# L002_-_Square_-_Schematic.net
KiCad netlist of a schematic drawn in EAGLE
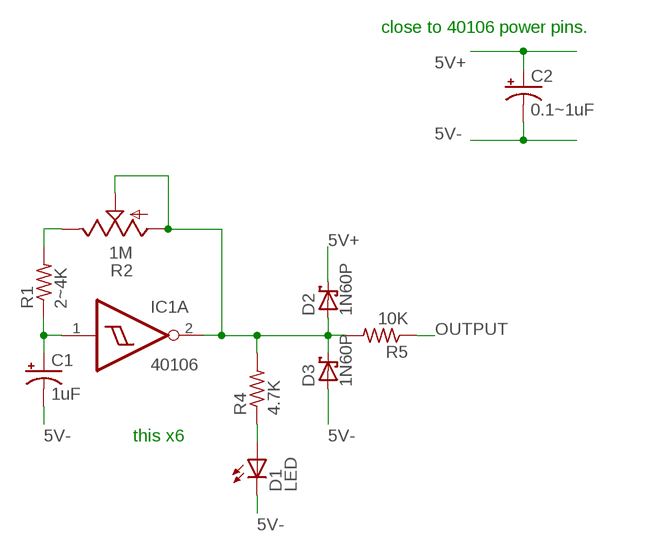
[diagram p0: schematic, sheet 1]

(export (version "E")
  (design (tool "Eeschema 10.0.6"))
  (components
    (comp (ref "C1")
      (value "1uF")
      (footprint "eagle-import:E2,5-6")
      (libsource (lib "eagle-import") (part "CPOL-USE2.5-6"))
    )
    (comp (ref "C2")
      (value "0.1~1uF")
      (footprint "eagle-import:E2,5-6")
      (libsource (lib "eagle-import") (part "CPOL-USE2.5-6"))
    )
    (comp (ref "D1")
      (value "LED")
      (footprint "eagle-import:SFH482")
      (libsource (lib "eagle-import") (part "SFH482"))
    )
    (comp (ref "D2")
      (value "1N60P")
      (footprint "eagle-import:DO41-7.6")
      (libsource (lib "eagle-import") (part "1N5817-B"))
    )
    (comp (ref "D3")
      (value "1N60P")
      (footprint "eagle-import:DO41-7.6")
      (libsource (lib "eagle-import") (part "1N5817-B"))
    )
    (comp (ref "IC1")
      (value "40106")
      (footprint "eagle-import:DIL14")
      (libsource (lib "eagle-import") (part "40106N"))
    )
    (comp (ref "R1")
      (value "2~4K")
      (footprint "eagle-import:VMTA55")
      (libsource (lib "eagle-import") (part "R-US_VMTA55"))
    )
    (comp (ref "R2")
      (value "1M")
      (footprint "eagle-import:EVUFXM")
      (libsource (lib "eagle-import") (part "US-EVUMF3"))
    )
    (comp (ref "R4")
      (value "4.7K")
      (footprint "eagle-import:VMTA55")
      (libsource (lib "eagle-import") (part "R-US_VMTA55"))
    )
    (comp (ref "R5")
      (value "10K")
      (footprint "eagle-import:VMTA55")
      (libsource (lib "eagle-import") (part "R-US_VMTA55"))
    )
  )
  (nets
    (net (code "1") (name "/5V+") (class "Default")
      (node (ref "C2") (pin "+") (pinfunction "+_+") (pintype "passive"))
      (node (ref "D2") (pin "C") (pinfunction "C_C") (pintype "passive"))
    )
    (net (code "2") (name "/5V-") (class "Default")
      (node (ref "C1") (pin "-") (pinfunction "-_-") (pintype "passive"))
      (node (ref "C2") (pin "-") (pinfunction "-_-") (pintype "passive"))
      (node (ref "D1") (pin "K") (pinfunction "C_K") (pintype "passive"))
      (node (ref "D3") (pin "A") (pinfunction "A_A") (pintype "passive"))
    )
    (net (code "3") (name "/OUTPUT") (class "Default")
      (node (ref "D2") (pin "A") (pinfunction "A_A") (pintype "passive"))
      (node (ref "D3") (pin "C") (pinfunction "C_C") (pintype "passive"))
      (node (ref "IC1") (pin "2") (pinfunction "O_2") (pintype "output"))
      (node (ref "R2") (pin "1") (pinfunction "A_1") (pintype "passive"))
      (node (ref "R2") (pin "2") (pinfunction "S_2") (pintype "passive"))
      (node (ref "R4") (pin "2") (pinfunction "2_2") (pintype "passive"))
      (node (ref "R5") (pin "1") (pinfunction "1_1") (pintype "passive"))
      (node (ref "R5") (pin "2") (pinfunction "2_2") (pintype "passive"))
    )
    (net (code "4") (name "Net-(D1-PadA)") (class "Default")
      (node (ref "D1") (pin "A") (pinfunction "A_A") (pintype "passive"))
      (node (ref "R4") (pin "1") (pinfunction "1_1") (pintype "passive"))
    )
    (net (code "5") (name "Net-(IC1A-I)") (class "Default")
      (node (ref "C1") (pin "+") (pinfunction "+_+") (pintype "passive"))
      (node (ref "IC1") (pin "1") (pinfunction "I_1") (pintype "input"))
      (node (ref "R1") (pin "1") (pinfunction "1_1") (pintype "passive"))
    )
    (net (code "6") (name "Net-(R2-E)") (class "Default")
      (node (ref "R1") (pin "2") (pinfunction "2_2") (pintype "passive"))
      (node (ref "R2") (pin "3") (pinfunction "E_3") (pintype "passive"))
    )
  )
)
